# touch-24-v3.net
KiCad netlist of a schematic drawn in Altium Designer
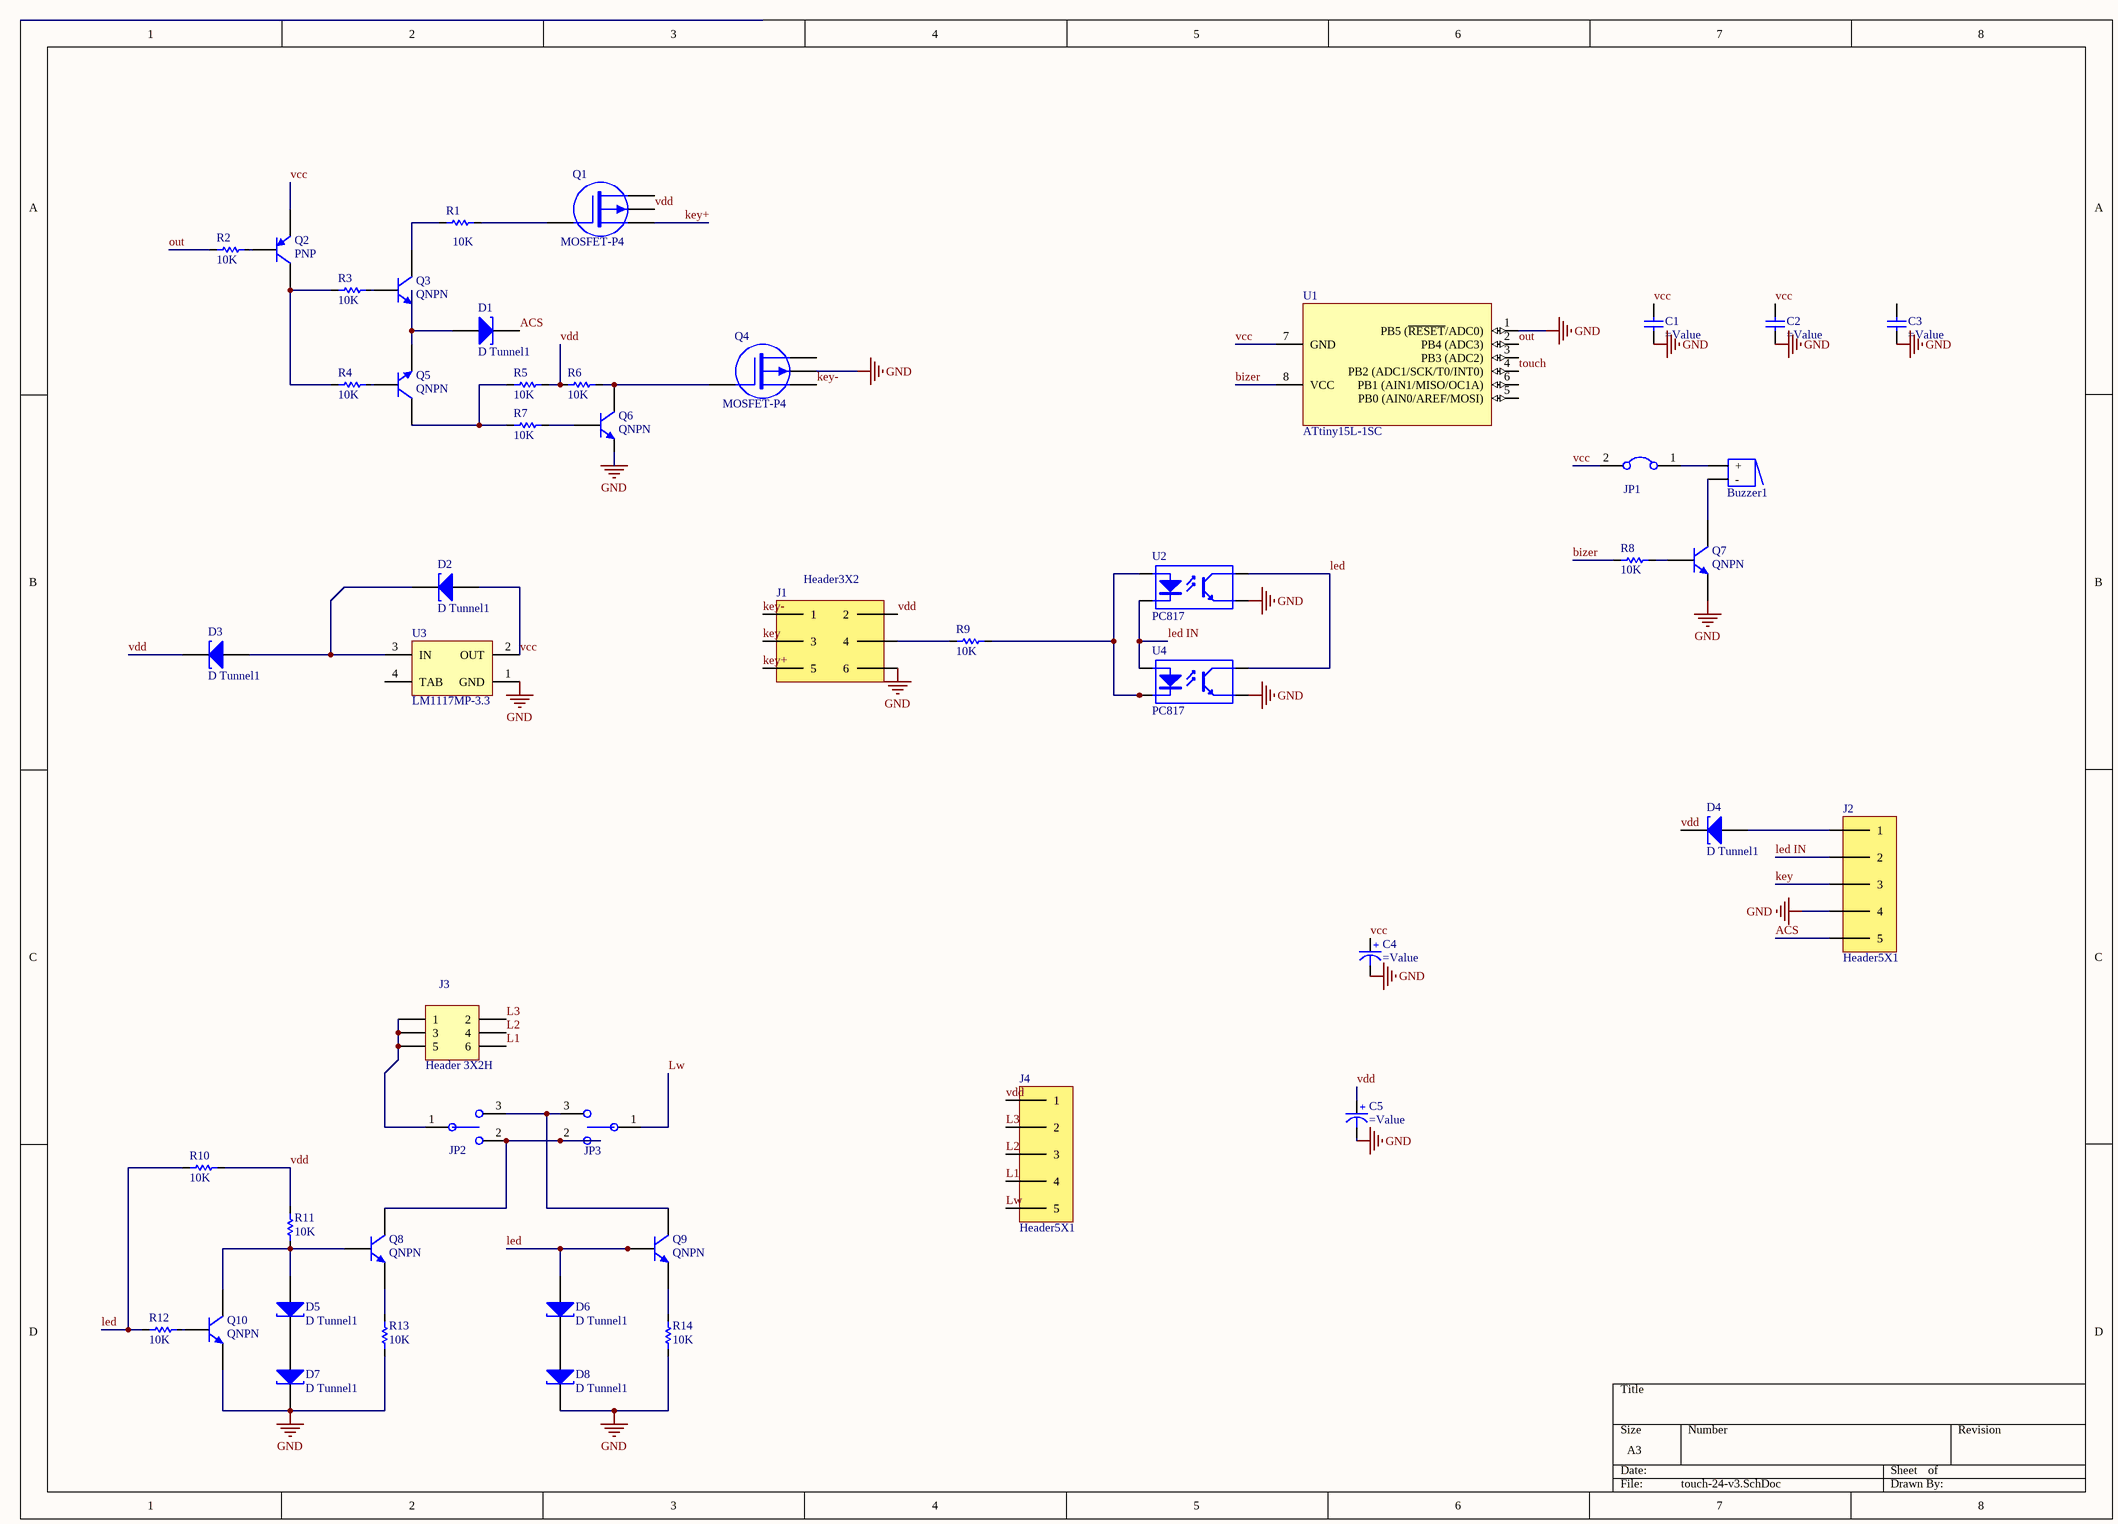
[diagram p0: touch-24-v3.SchDoc]

(export (version "E")
  (design (tool "Eeschema 10.0.6"))
  (components
    (comp (ref "Buzzer1")
      (value "Buzzer")
      (footprint "BUZZER")
      (fields (field (name "DESIGNER") "Seyed Mohsen Ghasemain"))
      (libsource (lib "PicPars.com_usefully_Library") (part "Buzzer"))
    )
    (comp (ref "C1")
      (value "~")
      (footprint "CAP 1206")
      (description "Capacitor")
      (libsource (lib "AltiumLib1") (part "Capacitor"))
    )
    (comp (ref "C2")
      (value "~")
      (footprint "CAP 1206")
      (description "Capacitor")
      (libsource (lib "AltiumLib1") (part "Capacitor"))
    )
    (comp (ref "C3")
      (value "~")
      (footprint "CAP 1206")
      (description "Capacitor")
      (libsource (lib "AltiumLib1") (part "Capacitor"))
    )
    (comp (ref "C4")
      (value "~")
      (footprint "ELEC-CAP-RAD10-20")
      (description "Electrolytic Capacitor")
      (libsource (lib "AltiumLib1") (part "Capacitor Electrolytic"))
    )
    (comp (ref "C5")
      (value "~")
      (footprint "ELEC-CAP-RAD15-30")
      (description "Electrolytic Capacitor")
      (libsource (lib "AltiumLib1") (part "Capacitor Electrolytic"))
    )
    (comp (ref "D1")
      (value "D Tunnel1")
      (footprint "3.2X1.6X1.1")
      (description "Tunnel Diode - RLC Model")
      (fields (field (name "PUBLISHER") "Altium Limited"))
      (libsource (lib "Miscellaneous Devices") (part "D Tunnel1"))
    )
    (comp (ref "D2")
      (value "D Tunnel1")
      (footprint "3.2X1.6X1.1")
      (description "Tunnel Diode - RLC Model")
      (fields (field (name "PUBLISHER") "Altium Limited"))
      (libsource (lib "Miscellaneous Devices") (part "D Tunnel1"))
    )
    (comp (ref "D3")
      (value "D Tunnel1")
      (footprint "3.2X1.6X1.1")
      (description "Tunnel Diode - RLC Model")
      (fields (field (name "PUBLISHER") "Altium Limited"))
      (libsource (lib "Miscellaneous Devices") (part "D Tunnel1"))
    )
    (comp (ref "D4")
      (value "D Tunnel1")
      (footprint "3.2X1.6X1.1")
      (description "Tunnel Diode - RLC Model")
      (fields (field (name "PUBLISHER") "Altium Limited"))
      (libsource (lib "Miscellaneous Devices") (part "D Tunnel1"))
    )
    (comp (ref "D5")
      (value "D Tunnel1")
      (footprint "3.2X1.6X1.1")
      (description "Tunnel Diode - RLC Model")
      (fields (field (name "PUBLISHER") "Altium Limited"))
      (libsource (lib "Miscellaneous Devices") (part "D Tunnel1"))
    )
    (comp (ref "D6")
      (value "D Tunnel1")
      (footprint "3.2X1.6X1.1")
      (description "Tunnel Diode - RLC Model")
      (fields (field (name "PUBLISHER") "Altium Limited"))
      (libsource (lib "Miscellaneous Devices") (part "D Tunnel1"))
    )
    (comp (ref "D7")
      (value "D Tunnel1")
      (footprint "3.2X1.6X1.1")
      (description "Tunnel Diode - RLC Model")
      (fields (field (name "PUBLISHER") "Altium Limited"))
      (libsource (lib "Miscellaneous Devices") (part "D Tunnel1"))
    )
    (comp (ref "D8")
      (value "D Tunnel1")
      (footprint "3.2X1.6X1.1")
      (description "Tunnel Diode - RLC Model")
      (fields (field (name "PUBLISHER") "Altium Limited"))
      (libsource (lib "Miscellaneous Devices") (part "D Tunnel1"))
    )
    (comp (ref "J1")
      (value "Header3X2")
      (footprint "HEADER 3X2")
      (libsource (lib "AltiumLib1") (part "Header3X2"))
    )
    (comp (ref "J2")
      (value "Header5X1")
      (footprint "HEADER 5X1")
      (libsource (lib "AltiumLib1") (part "Header5X1"))
    )
    (comp (ref "J3")
      (value "Header 3X2H")
      (footprint "HDR2X3H")
      (description "Header, 3-Pin, Dual row, Right Angle")
      (fields (field (name "PUBLISHER") "Altium Limited"))
      (libsource (lib "Miscellaneous Connectors") (part "Header 3X2H"))
    )
    (comp (ref "J4")
      (value "Header5X1")
      (footprint "HEADER 5X1")
      (libsource (lib "AltiumLib1") (part "Header5X1"))
    )
    (comp (ref "JP1")
      (value "Jumper")
      (footprint "Header 2X1")
      (libsource (lib "AltiumLib1") (part "Jumper"))
    )
    (comp (ref "JP2")
      (value "Jumper Selector")
      (footprint "Jumper Selector")
      (libsource (lib "AltiumLib1") (part "Jumper Selector"))
    )
    (comp (ref "JP3")
      (value "Jumper Selector")
      (footprint "Jumper Selector")
      (libsource (lib "") (part "Jumper Selector_1"))
    )
    (comp (ref "Q1")
      (value "MOSFET-P4")
      (footprint "SOT223_N")
      (description "P-Channel MOSFET, Externally Terminated Substrate")
      (fields (field (name "PUBLISHER") "Altium Limited"))
      (libsource (lib "Miscellaneous Devices") (part "MOSFET-P4"))
    )
    (comp (ref "Q2")
      (value "PNP")
      (footprint "SOT-23B_N")
      (description "PNP Bipolar Transistor")
      (fields (field (name "PUBLISHER") "Altium Limited"))
      (libsource (lib "Miscellaneous Devices") (part "PNP"))
    )
    (comp (ref "Q3")
      (value "QNPN")
      (footprint "SOT-23B_L")
      (description "NPN Bipolar Transistor")
      (fields (field (name "PUBLISHER") "Altium Limited"))
      (libsource (lib "Miscellaneous Devices") (part "QNPN"))
    )
    (comp (ref "Q4")
      (value "MOSFET-P4")
      (footprint "SOT223_N")
      (description "P-Channel MOSFET, Externally Terminated Substrate")
      (fields (field (name "PUBLISHER") "Altium Limited"))
      (libsource (lib "Miscellaneous Devices") (part "MOSFET-P4"))
    )
    (comp (ref "Q5")
      (value "QNPN")
      (footprint "SOT-23B_L")
      (description "NPN Bipolar Transistor")
      (fields (field (name "PUBLISHER") "Altium Limited"))
      (libsource (lib "Miscellaneous Devices") (part "QNPN"))
    )
    (comp (ref "Q6")
      (value "QNPN")
      (footprint "SOT-23B_L")
      (description "NPN Bipolar Transistor")
      (fields (field (name "PUBLISHER") "Altium Limited"))
      (libsource (lib "Miscellaneous Devices") (part "QNPN"))
    )
    (comp (ref "Q7")
      (value "QNPN")
      (footprint "SOT-23B_L")
      (description "NPN Bipolar Transistor")
      (fields (field (name "PUBLISHER") "Altium Limited"))
      (libsource (lib "Miscellaneous Devices") (part "QNPN"))
    )
    (comp (ref "Q8")
      (value "QNPN")
      (footprint "SOT-23B_L")
      (description "NPN Bipolar Transistor")
      (fields (field (name "PUBLISHER") "Altium Limited"))
      (libsource (lib "Miscellaneous Devices") (part "QNPN"))
    )
    (comp (ref "Q9")
      (value "QNPN")
      (footprint "SOT-23B_L")
      (description "NPN Bipolar Transistor")
      (fields (field (name "PUBLISHER") "Altium Limited"))
      (libsource (lib "Miscellaneous Devices") (part "QNPN"))
    )
    (comp (ref "Q10")
      (value "QNPN")
      (footprint "SOT-23B_L")
      (description "NPN Bipolar Transistor")
      (fields (field (name "PUBLISHER") "Altium Limited"))
      (libsource (lib "Miscellaneous Devices") (part "QNPN"))
    )
    (comp (ref "R1")
      (value "10K")
      (footprint "RES 1206 (3216X08L)")
      (description "Resistor")
      (fields (field (name "TOLERANCE") "5%") (field (name "POWER") "1/4 W"))
      (libsource (lib "AltiumLib1") (part "Resistor"))
    )
    (comp (ref "R2")
      (value "10K")
      (footprint "RES 1206 (3216X08L)")
      (description "Resistor")
      (fields (field (name "TOLERANCE") "5%") (field (name "POWER") "1/4 W"))
      (libsource (lib "AltiumLib1") (part "Resistor"))
    )
    (comp (ref "R3")
      (value "10K")
      (footprint "RES 1206 (3216X08L)")
      (description "Resistor")
      (fields (field (name "TOLERANCE") "5%") (field (name "POWER") "1/4 W"))
      (libsource (lib "AltiumLib1") (part "Resistor"))
    )
    (comp (ref "R4")
      (value "10K")
      (footprint "RES 1206 (3216X08L)")
      (description "Resistor")
      (fields (field (name "TOLERANCE") "5%") (field (name "POWER") "1/4 W"))
      (libsource (lib "AltiumLib1") (part "Resistor"))
    )
    (comp (ref "R5")
      (value "10K")
      (footprint "RES 1206 (3216X08L)")
      (description "Resistor")
      (fields (field (name "TOLERANCE") "5%") (field (name "POWER") "1/4 W"))
      (libsource (lib "AltiumLib1") (part "Resistor"))
    )
    (comp (ref "R6")
      (value "10K")
      (footprint "RES 1206 (3216X08L)")
      (description "Resistor")
      (fields (field (name "TOLERANCE") "5%") (field (name "POWER") "1/4 W"))
      (libsource (lib "AltiumLib1") (part "Resistor"))
    )
    (comp (ref "R7")
      (value "10K")
      (footprint "RES 1206 (3216X08L)")
      (description "Resistor")
      (fields (field (name "TOLERANCE") "5%") (field (name "POWER") "1/4 W"))
      (libsource (lib "AltiumLib1") (part "Resistor"))
    )
    (comp (ref "R8")
      (value "10K")
      (footprint "RES 1206 (3216X08L)")
      (description "Resistor")
      (fields (field (name "TOLERANCE") "5%") (field (name "POWER") "1/4 W"))
      (libsource (lib "AltiumLib1") (part "Resistor"))
    )
    (comp (ref "R9")
      (value "10K")
      (footprint "RES 1206 (3216X08L)")
      (description "Resistor")
      (fields (field (name "TOLERANCE") "5%") (field (name "POWER") "1/4 W"))
      (libsource (lib "AltiumLib1") (part "Resistor"))
    )
    (comp (ref "R10")
      (value "10K")
      (footprint "RES 1206 (3216X08L)")
      (description "Resistor")
      (fields (field (name "TOLERANCE") "5%") (field (name "POWER") "1/4 W"))
      (libsource (lib "AltiumLib1") (part "Resistor"))
    )
    (comp (ref "R11")
      (value "10K")
      (footprint "RES 1206 (3216X08L)")
      (description "Resistor")
      (fields (field (name "TOLERANCE") "5%") (field (name "POWER") "1/4 W"))
      (libsource (lib "AltiumLib1") (part "Resistor"))
    )
    (comp (ref "R12")
      (value "10K")
      (footprint "RES 1206 (3216X08L)")
      (description "Resistor")
      (fields (field (name "TOLERANCE") "5%") (field (name "POWER") "1/4 W"))
      (libsource (lib "AltiumLib1") (part "Resistor"))
    )
    (comp (ref "R13")
      (value "10K")
      (footprint "RES 1206 (3216X08L)")
      (description "Resistor")
      (fields (field (name "TOLERANCE") "5%") (field (name "POWER") "1/4 W"))
      (libsource (lib "AltiumLib1") (part "Resistor"))
    )
    (comp (ref "R14")
      (value "10K")
      (footprint "RES 1206 (3216X08L)")
      (description "Resistor")
      (fields (field (name "TOLERANCE") "5%") (field (name "POWER") "1/4 W"))
      (libsource (lib "AltiumLib1") (part "Resistor"))
    )
    (comp (ref "U1")
      (value "ATtiny15L-1SC")
      (footprint "8S2_N")
      (description "8-Bit AVR Microcontroller with 1K Byte of Flash Memory")
      (fields (field (name "PUBLISHER") "Altium Limited"))
      (libsource (lib "Atmel Microcontroller 8-Bit AVR") (part "ATtiny15L-1SC"))
    )
    (comp (ref "U2")
      (value "PC817")
      (footprint "DIP4")
      (description "4-Pin Phototransistor Optocoupler")
      (libsource (lib "AltiumLib1") (part "OPTCOUPLER_01"))
    )
    (comp (ref "U3")
      (value "LM1117MP-3.3")
      (footprint "Miscellaneous Devices:SOT89L")
      (description "800mA Low-Dropout Linear Regulator")
      (fields
        (field (name "MANUFACTURER") "National Semiconductor")
        (field (name "DIGIKEYPARTNUMBER") "LM1117MP-3.3CT-ND")
        (field (name "PUBLISHER") "Altium Limited")
      )
      (libsource (lib "NSC LDO") (part "LM1117MP-3.3"))
    )
    (comp (ref "U4")
      (value "PC817")
      (footprint "DIP4")
      (description "4-Pin Phototransistor Optocoupler")
      (libsource (lib "AltiumLib1") (part "OPTCOUPLER_01"))
    )
  )
  (nets
    (net (code "1") (name "/ACS") (class "Default")
      (node (ref "D1") (pin "2") (pinfunction "K_2") (pintype "passive"))
      (node (ref "J2") (pin "5") (pinfunction "5_5") (pintype "passive"))
    )
    (net (code "2") (name "/L1") (class "Default")
      (node (ref "J3") (pin "6") (pinfunction "6_6") (pintype "passive"))
      (node (ref "J4") (pin "4") (pinfunction "4_4") (pintype "passive"))
    )
    (net (code "3") (name "/L2") (class "Default")
      (node (ref "J3") (pin "4") (pinfunction "4_4") (pintype "passive"))
      (node (ref "J4") (pin "3") (pinfunction "3_3") (pintype "passive"))
    )
    (net (code "4") (name "/L3") (class "Default")
      (node (ref "J3") (pin "2") (pinfunction "2_2") (pintype "passive"))
      (node (ref "J4") (pin "2") (pinfunction "2_2") (pintype "passive"))
    )
    (net (code "5") (name "/Lw") (class "Default")
      (node (ref "J4") (pin "5") (pinfunction "5_5") (pintype "passive"))
      (node (ref "JP3") (pin "1") (pinfunction "1_1") (pintype "passive"))
    )
    (net (code "6") (name "/bizer") (class "Default")
      (node (ref "R8") (pin "1") (pinfunction "1_1") (pintype "passive"))
      (node (ref "U1") (pin "8") (pinfunction "VCC_8") (pintype "power_in"))
    )
    (net (code "7") (name "/key") (class "Default")
      (node (ref "J1") (pin "3") (pinfunction "3_3") (pintype "passive"))
      (node (ref "J2") (pin "3") (pinfunction "3_3") (pintype "passive"))
    )
    (net (code "8") (name "/key+") (class "Default")
      (node (ref "J1") (pin "5") (pinfunction "5_5") (pintype "passive"))
      (node (ref "Q1") (pin "4") (pinfunction "S_4") (pintype "passive"))
    )
    (net (code "9") (name "/key-") (class "Default")
      (node (ref "J1") (pin "1") (pinfunction "1_1") (pintype "passive"))
      (node (ref "Q4") (pin "4") (pinfunction "S_4") (pintype "passive"))
    )
    (net (code "10") (name "/led") (class "Default")
      (node (ref "D6") (pin "1") (pinfunction "A_1") (pintype "passive"))
      (node (ref "Q9") (pin "2") (pinfunction "B_2") (pintype "passive"))
      (node (ref "R10") (pin "1") (pinfunction "1_1") (pintype "passive"))
      (node (ref "R12") (pin "1") (pinfunction "1_1") (pintype "passive"))
      (node (ref "U2") (pin "4") (pinfunction "C_4") (pintype "passive"))
      (node (ref "U4") (pin "4") (pinfunction "C_4") (pintype "passive"))
    )
    (net (code "11") (name "/led IN") (class "Default")
      (node (ref "J2") (pin "2") (pinfunction "2_2") (pintype "passive"))
      (node (ref "U2") (pin "2") (pinfunction "K_2") (pintype "passive"))
      (node (ref "U4") (pin "1") (pinfunction "A_1") (pintype "passive"))
    )
    (net (code "12") (name "/out") (class "Default")
      (node (ref "R2") (pin "1") (pinfunction "1_1") (pintype "passive"))
      (node (ref "U1") (pin "2") (pinfunction "PB4_(ADC3)_2") (pintype "bidirectional"))
    )
    (net (code "13") (name "/touch") (class "Default")
      (node (ref "U1") (pin "4") (pinfunction "PB2_(ADC1/SCK/T0/INT0)_4") (pintype "bidirectional"))
    )
    (net (code "14") (name "/vcc") (class "Default")
      (node (ref "C1") (pin "2") (pinfunction "-_2") (pintype "passive"))
      (node (ref "C2") (pin "2") (pinfunction "-_2") (pintype "passive"))
      (node (ref "C4") (pin "2") (pinfunction "+_2") (pintype "passive"))
      (node (ref "D2") (pin "1") (pinfunction "A_1") (pintype "passive"))
      (node (ref "JP1") (pin "2") (pinfunction "2_2") (pintype "passive"))
      (node (ref "Q2") (pin "3") (pinfunction "E_3") (pintype "passive"))
      (node (ref "U1") (pin "7") (pinfunction "GND_7") (pintype "power_in"))
      (node (ref "U3") (pin "2") (pinfunction "OUT_2") (pintype "power_in"))
    )
    (net (code "15") (name "/vdd") (class "Default")
      (node (ref "C5") (pin "2") (pinfunction "+_2") (pintype "passive"))
      (node (ref "D3") (pin "2") (pinfunction "K_2") (pintype "passive"))
      (node (ref "D4") (pin "2") (pinfunction "K_2") (pintype "passive"))
      (node (ref "J1") (pin "2") (pinfunction "2_2") (pintype "passive"))
      (node (ref "J4") (pin "1") (pinfunction "1_1") (pintype "passive"))
      (node (ref "Q1") (pin "3") (pinfunction "U_3") (pintype "passive"))
      (node (ref "R10") (pin "2") (pinfunction "2_2") (pintype "passive"))
      (node (ref "R11") (pin "2") (pinfunction "2_2") (pintype "passive"))
      (node (ref "R5") (pin "2") (pinfunction "2_2") (pintype "passive"))
      (node (ref "R6") (pin "1") (pinfunction "1_1") (pintype "passive"))
    )
    (net (code "16") (name "GND") (class "Default")
      (node (ref "C1") (pin "1") (pinfunction "+_1") (pintype "passive"))
      (node (ref "C2") (pin "1") (pinfunction "+_1") (pintype "passive"))
      (node (ref "C3") (pin "1") (pinfunction "+_1") (pintype "passive"))
      (node (ref "C4") (pin "1") (pinfunction "-_1") (pintype "passive"))
      (node (ref "C5") (pin "1") (pinfunction "-_1") (pintype "passive"))
      (node (ref "D7") (pin "2") (pinfunction "K_2") (pintype "passive"))
      (node (ref "D8") (pin "2") (pinfunction "K_2") (pintype "passive"))
      (node (ref "J1") (pin "6") (pinfunction "6_6") (pintype "passive"))
      (node (ref "J2") (pin "4") (pinfunction "4_4") (pintype "passive"))
      (node (ref "Q10") (pin "3") (pinfunction "E_3") (pintype "passive"))
      (node (ref "Q4") (pin "3") (pinfunction "U_3") (pintype "passive"))
      (node (ref "Q6") (pin "3") (pinfunction "E_3") (pintype "passive"))
      (node (ref "Q7") (pin "3") (pinfunction "E_3") (pintype "passive"))
      (node (ref "R13") (pin "1") (pinfunction "1_1") (pintype "passive"))
      (node (ref "R14") (pin "1") (pinfunction "1_1") (pintype "passive"))
      (node (ref "U1") (pin "1") (pinfunction "PB5_(~{RESET}/ADC0)_1") (pintype "bidirectional"))
      (node (ref "U2") (pin "3") (pinfunction "E_3") (pintype "passive"))
      (node (ref "U3") (pin "1") (pinfunction "GND_1") (pintype "power_in"))
      (node (ref "U4") (pin "3") (pinfunction "E_3") (pintype "passive"))
    )
    (net (code "17") (name "Net-(Buzzer1-+)") (class "Default")
      (node (ref "Buzzer1") (pin "1") (pinfunction "+_1") (pintype "passive"))
      (node (ref "JP1") (pin "1") (pinfunction "1_1") (pintype "passive"))
    )
    (net (code "18") (name "Net-(Buzzer1--)") (class "Default")
      (node (ref "Buzzer1") (pin "2") (pinfunction "-_2") (pintype "passive"))
      (node (ref "Q7") (pin "1") (pinfunction "C_1") (pintype "passive"))
    )
    (net (code "19") (name "Net-(D1-A)") (class "Default")
      (node (ref "D1") (pin "1") (pinfunction "A_1") (pintype "passive"))
      (node (ref "Q3") (pin "3") (pinfunction "E_3") (pintype "passive"))
      (node (ref "Q5") (pin "3") (pinfunction "E_3") (pintype "passive"))
    )
    (net (code "20") (name "Net-(D2-K)") (class "Default")
      (node (ref "D2") (pin "2") (pinfunction "K_2") (pintype "passive"))
      (node (ref "D3") (pin "1") (pinfunction "A_1") (pintype "passive"))
      (node (ref "U3") (pin "3") (pinfunction "IN_3") (pintype "power_in"))
    )
    (net (code "21") (name "Net-(D4-A)") (class "Default")
      (node (ref "D4") (pin "1") (pinfunction "A_1") (pintype "passive"))
      (node (ref "J2") (pin "1") (pinfunction "1_1") (pintype "passive"))
    )
    (net (code "22") (name "Net-(D5-A)") (class "Default")
      (node (ref "D5") (pin "1") (pinfunction "A_1") (pintype "passive"))
      (node (ref "Q10") (pin "1") (pinfunction "C_1") (pintype "passive"))
      (node (ref "Q8") (pin "2") (pinfunction "B_2") (pintype "passive"))
      (node (ref "R11") (pin "1") (pinfunction "1_1") (pintype "passive"))
    )
    (net (code "23") (name "Net-(D5-K)") (class "Default")
      (node (ref "D5") (pin "2") (pinfunction "K_2") (pintype "passive"))
      (node (ref "D7") (pin "1") (pinfunction "A_1") (pintype "passive"))
    )
    (net (code "24") (name "Net-(D6-K)") (class "Default")
      (node (ref "D6") (pin "2") (pinfunction "K_2") (pintype "passive"))
      (node (ref "D8") (pin "1") (pinfunction "A_1") (pintype "passive"))
    )
    (net (code "25") (name "Net-(J1-Pad4)") (class "Default")
      (node (ref "J1") (pin "4") (pinfunction "4_4") (pintype "passive"))
      (node (ref "R9") (pin "1") (pinfunction "1_1") (pintype "passive"))
    )
    (net (code "26") (name "Net-(J3-Pad1)") (class "Default")
      (node (ref "J3") (pin "1") (pinfunction "1_1") (pintype "passive"))
      (node (ref "J3") (pin "3") (pinfunction "3_3") (pintype "passive"))
      (node (ref "J3") (pin "5") (pinfunction "5_5") (pintype "passive"))
      (node (ref "JP2") (pin "1") (pinfunction "1_1") (pintype "passive"))
    )
    (net (code "27") (name "Net-(Q1-G)") (class "Default")
      (node (ref "Q1") (pin "1") (pinfunction "G_1") (pintype "passive"))
      (node (ref "R1") (pin "2") (pinfunction "2_2") (pintype "passive"))
    )
    (net (code "28") (name "Net-(Q2-B)") (class "Default")
      (node (ref "Q2") (pin "2") (pinfunction "B_2") (pintype "passive"))
      (node (ref "R2") (pin "2") (pinfunction "2_2") (pintype "passive"))
    )
    (net (code "29") (name "Net-(Q2-C)") (class "Default")
      (node (ref "Q2") (pin "1") (pinfunction "C_1") (pintype "passive"))
      (node (ref "R3") (pin "1") (pinfunction "1_1") (pintype "passive"))
      (node (ref "R4") (pin "1") (pinfunction "1_1") (pintype "passive"))
    )
    (net (code "30") (name "Net-(Q3-B)") (class "Default")
      (node (ref "Q3") (pin "2") (pinfunction "B_2") (pintype "passive"))
      (node (ref "R3") (pin "2") (pinfunction "2_2") (pintype "passive"))
    )
    (net (code "31") (name "Net-(Q3-C)") (class "Default")
      (node (ref "Q3") (pin "1") (pinfunction "C_1") (pintype "passive"))
      (node (ref "R1") (pin "1") (pinfunction "1_1") (pintype "passive"))
    )
    (net (code "32") (name "Net-(Q4-G)") (class "Default")
      (node (ref "Q4") (pin "1") (pinfunction "G_1") (pintype "passive"))
      (node (ref "Q6") (pin "1") (pinfunction "C_1") (pintype "passive"))
      (node (ref "R6") (pin "2") (pinfunction "2_2") (pintype "passive"))
    )
    (net (code "33") (name "Net-(Q5-B)") (class "Default")
      (node (ref "Q5") (pin "2") (pinfunction "B_2") (pintype "passive"))
      (node (ref "R4") (pin "2") (pinfunction "2_2") (pintype "passive"))
    )
    (net (code "34") (name "Net-(Q5-C)") (class "Default")
      (node (ref "Q5") (pin "1") (pinfunction "C_1") (pintype "passive"))
      (node (ref "R5") (pin "1") (pinfunction "1_1") (pintype "passive"))
      (node (ref "R7") (pin "1") (pinfunction "1_1") (pintype "passive"))
    )
    (net (code "35") (name "Net-(Q6-B)") (class "Default")
      (node (ref "Q6") (pin "2") (pinfunction "B_2") (pintype "passive"))
      (node (ref "R7") (pin "2") (pinfunction "2_2") (pintype "passive"))
    )
    (net (code "36") (name "Net-(Q7-B)") (class "Default")
      (node (ref "Q7") (pin "2") (pinfunction "B_2") (pintype "passive"))
      (node (ref "R8") (pin "2") (pinfunction "2_2") (pintype "passive"))
    )
    (net (code "37") (name "Net-(Q8-C)") (class "Default")
      (node (ref "JP2") (pin "2") (pinfunction "2_2") (pintype "passive"))
      (node (ref "JP3") (pin "2") (pinfunction "2_2") (pintype "passive"))
      (node (ref "Q8") (pin "1") (pinfunction "C_1") (pintype "passive"))
    )
    (net (code "38") (name "Net-(Q8-E)") (class "Default")
      (node (ref "Q8") (pin "3") (pinfunction "E_3") (pintype "passive"))
      (node (ref "R13") (pin "2") (pinfunction "2_2") (pintype "passive"))
    )
    (net (code "39") (name "Net-(Q9-C)") (class "Default")
      (node (ref "JP2") (pin "3") (pinfunction "3_3") (pintype "passive"))
      (node (ref "JP3") (pin "3") (pinfunction "3_3") (pintype "passive"))
      (node (ref "Q9") (pin "1") (pinfunction "C_1") (pintype "passive"))
    )
    (net (code "40") (name "Net-(Q9-E)") (class "Default")
      (node (ref "Q9") (pin "3") (pinfunction "E_3") (pintype "passive"))
      (node (ref "R14") (pin "2") (pinfunction "2_2") (pintype "passive"))
    )
    (net (code "41") (name "Net-(Q10-B)") (class "Default")
      (node (ref "Q10") (pin "2") (pinfunction "B_2") (pintype "passive"))
      (node (ref "R12") (pin "2") (pinfunction "2_2") (pintype "passive"))
    )
    (net (code "42") (name "Net-(U2-A)") (class "Default")
      (node (ref "R9") (pin "2") (pinfunction "2_2") (pintype "passive"))
      (node (ref "U2") (pin "1") (pinfunction "A_1") (pintype "passive"))
      (node (ref "U4") (pin "2") (pinfunction "K_2") (pintype "passive"))
    )
    (net (code "43") (name "unconnected-(C3---Pad2)") (class "Default")
      (node (ref "C3") (pin "2") (pinfunction "-_2") (pintype "passive"))
    )
    (net (code "44") (name "unconnected-(Q1-D-Pad2)") (class "Default")
      (node (ref "Q1") (pin "2") (pinfunction "D_2") (pintype "passive"))
    )
    (net (code "45") (name "unconnected-(Q4-D-Pad2)") (class "Default")
      (node (ref "Q4") (pin "2") (pinfunction "D_2") (pintype "passive"))
    )
    (net (code "46") (name "unconnected-(U1-PB0_(AIN0{slash}AREF{slash}MOSI)-Pad5)") (class "Default")
      (node (ref "U1") (pin "5") (pinfunction "PB0_(AIN0/AREF/MOSI)_5") (pintype "bidirectional"))
    )
    (net (code "47") (name "unconnected-(U1-PB1_(AIN1{slash}MISO{slash}OC1A)-Pad6)") (class "Default")
      (node (ref "U1") (pin "6") (pinfunction "PB1_(AIN1/MISO/OC1A)_6") (pintype "bidirectional"))
    )
    (net (code "48") (name "unconnected-(U1-PB3_(ADC2)-Pad3)") (class "Default")
      (node (ref "U1") (pin "3") (pinfunction "PB3_(ADC2)_3") (pintype "bidirectional"))
    )
    (net (code "49") (name "unconnected-(U3-TAB-Pad4)") (class "Default")
      (node (ref "U3") (pin "4") (pinfunction "TAB_4") (pintype "power_in"))
    )
  )
)
